# nightLight.net
KiCad netlist of a schematic drawn in EAGLE
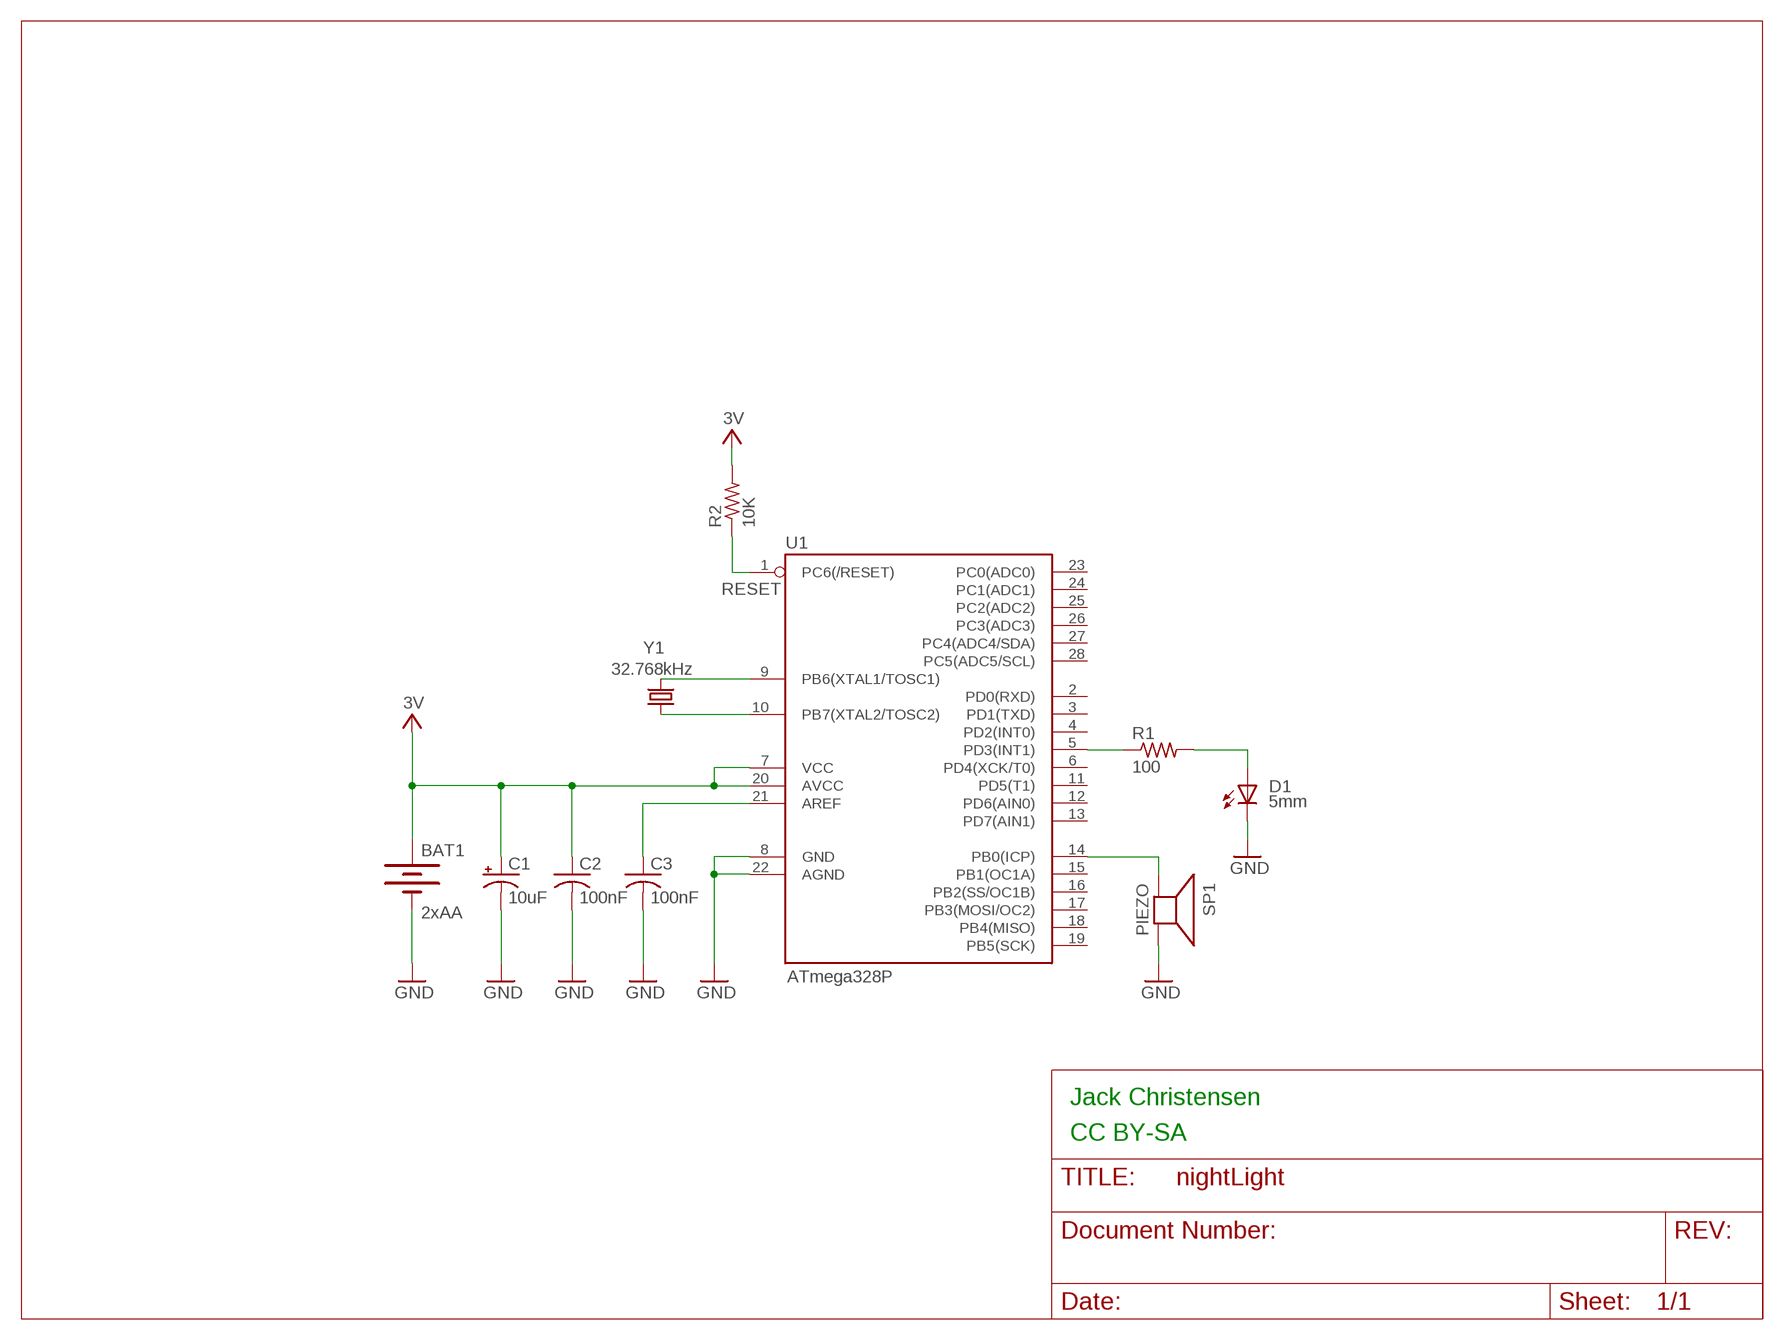
[diagram p0: schematic, sheet 1]

(export (version "E")
  (design (tool "Eeschema 10.0.6"))
  (components
    (comp (ref "BAT1")
      (value "2xAA")
      (footprint "eagle-import:BATTERY-AA")
      (libsource (lib "eagle-import") (part "BATTERYAA"))
    )
    (comp (ref "C1")
      (value "10uF")
      (footprint "eagle-import:E5-4")
      (libsource (lib "eagle-import") (part "CPOL-USE5-4"))
    )
    (comp (ref "C2")
      (value "100nF")
      (footprint "eagle-import:C025-025X050")
      (libsource (lib "eagle-import") (part "C-US025-025X050"))
    )
    (comp (ref "C3")
      (value "100nF")
      (footprint "eagle-import:C025-025X050")
      (libsource (lib "eagle-import") (part "C-US025-025X050"))
    )
    (comp (ref "D1")
      (value "5mm")
      (footprint "eagle-import:LED5MM")
      (libsource (lib "eagle-import") (part "LED5MM"))
    )
    (comp (ref "R1")
      (value "100")
      (footprint "eagle-import:0204_6")
      (libsource (lib "eagle-import") (part "R-US_0204/6"))
    )
    (comp (ref "R2")
      (value "10K")
      (footprint "eagle-import:0204_6")
      (libsource (lib "eagle-import") (part "R-US_0204/6"))
    )
    (comp (ref "SP1")
      (value "PIEZO")
      (footprint "eagle-import:AL11P")
      (libsource (lib "eagle-import") (part "SPEAKER/AL11P"))
    )
    (comp (ref "U1")
      (value "ATmega328P")
      (footprint "eagle-import:DIL28-3")
      (libsource (lib "eagle-import") (part "AVR-MEGA8-PPTH"))
    )
    (comp (ref "Y1")
      (value "32.768kHz")
      (footprint "eagle-import:TC38H")
      (libsource (lib "eagle-import") (part "CRYSTALTC38H"))
    )
  )
  (nets
    (net (code "1") (name "/RESET") (class "Default")
      (node (ref "R2") (pin "1") (pinfunction "1_1") (pintype "passive"))
      (node (ref "U1") (pin "1") (pinfunction "PC6(/RESET)_1") (pintype "bidirectional"))
    )
    (net (code "2") (name "3V") (class "Default")
      (node (ref "BAT1") (pin "PWR@1") (pinfunction "+_PWR@1") (pintype "power_in"))
      (node (ref "C1") (pin "+") (pinfunction "+_+") (pintype "passive"))
      (node (ref "C2") (pin "1") (pinfunction "1_1") (pintype "passive"))
      (node (ref "R2") (pin "2") (pinfunction "2_2") (pintype "passive"))
      (node (ref "U1") (pin "20") (pinfunction "AVCC_20") (pintype "bidirectional"))
      (node (ref "U1") (pin "7") (pinfunction "VCC_7") (pintype "bidirectional"))
    )
    (net (code "3") (name "GND") (class "Default")
      (node (ref "BAT1") (pin "GND@1") (pinfunction "-_GND@1") (pintype "power_in"))
      (node (ref "C1") (pin "-") (pinfunction "-_-") (pintype "passive"))
      (node (ref "C2") (pin "2") (pinfunction "2_2") (pintype "passive"))
      (node (ref "C3") (pin "2") (pinfunction "2_2") (pintype "passive"))
      (node (ref "D1") (pin "K") (pinfunction "C_K") (pintype "passive"))
      (node (ref "SP1") (pin "-") (pinfunction "-_-") (pintype "passive"))
      (node (ref "U1") (pin "22") (pinfunction "AGND_22") (pintype "bidirectional"))
      (node (ref "U1") (pin "8") (pinfunction "GND_8") (pintype "bidirectional"))
    )
    (net (code "4") (name "Net-(D1-PadA)") (class "Default")
      (node (ref "D1") (pin "A") (pinfunction "A_A") (pintype "passive"))
      (node (ref "R1") (pin "2") (pinfunction "2_2") (pintype "passive"))
    )
    (net (code "5") (name "Net-(U1-AREF)") (class "Default")
      (node (ref "C3") (pin "1") (pinfunction "1_1") (pintype "passive"))
      (node (ref "U1") (pin "21") (pinfunction "AREF_21") (pintype "bidirectional"))
    )
    (net (code "6") (name "Net-(U1-PB0(ICP))") (class "Default")
      (node (ref "SP1") (pin "+") (pinfunction "+_+") (pintype "passive"))
      (node (ref "U1") (pin "14") (pinfunction "PB0(ICP)_14") (pintype "bidirectional"))
    )
    (net (code "7") (name "Net-(U1-PB6(XTAL1{slash}TOSC1))") (class "Default")
      (node (ref "U1") (pin "9") (pinfunction "PB6(XTAL1/TOSC1)_9") (pintype "bidirectional"))
      (node (ref "Y1") (pin "2") (pinfunction "2_2") (pintype "passive"))
    )
    (net (code "8") (name "Net-(U1-PB7(XTAL2{slash}TOSC2))") (class "Default")
      (node (ref "U1") (pin "10") (pinfunction "PB7(XTAL2/TOSC2)_10") (pintype "bidirectional"))
      (node (ref "Y1") (pin "1") (pinfunction "1_1") (pintype "passive"))
    )
    (net (code "9") (name "Net-(U1-PD3(INT1))") (class "Default")
      (node (ref "R1") (pin "1") (pinfunction "1_1") (pintype "passive"))
      (node (ref "U1") (pin "5") (pinfunction "PD3(INT1)_5") (pintype "bidirectional"))
    )
    (net (code "10") (name "unconnected-(U1-PB1(OC1A)-Pad15)") (class "Default")
      (node (ref "U1") (pin "15") (pinfunction "PB1(OC1A)_15") (pintype "bidirectional"))
    )
    (net (code "11") (name "unconnected-(U1-PB2(SS{slash}OC1B)-Pad16)") (class "Default")
      (node (ref "U1") (pin "16") (pinfunction "PB2(SS/OC1B)_16") (pintype "bidirectional"))
    )
    (net (code "12") (name "unconnected-(U1-PB3(MOSI{slash}OC2)-Pad17)") (class "Default")
      (node (ref "U1") (pin "17") (pinfunction "PB3(MOSI/OC2)_17") (pintype "bidirectional"))
    )
    (net (code "13") (name "unconnected-(U1-PB4(MISO)-Pad18)") (class "Default")
      (node (ref "U1") (pin "18") (pinfunction "PB4(MISO)_18") (pintype "bidirectional"))
    )
    (net (code "14") (name "unconnected-(U1-PB5(SCK)-Pad19)") (class "Default")
      (node (ref "U1") (pin "19") (pinfunction "PB5(SCK)_19") (pintype "bidirectional"))
    )
    (net (code "15") (name "unconnected-(U1-PC0(ADC0)-Pad23)") (class "Default")
      (node (ref "U1") (pin "23") (pinfunction "PC0(ADC0)_23") (pintype "bidirectional"))
    )
    (net (code "16") (name "unconnected-(U1-PC1(ADC1)-Pad24)") (class "Default")
      (node (ref "U1") (pin "24") (pinfunction "PC1(ADC1)_24") (pintype "bidirectional"))
    )
    (net (code "17") (name "unconnected-(U1-PC2(ADC2)-Pad25)") (class "Default")
      (node (ref "U1") (pin "25") (pinfunction "PC2(ADC2)_25") (pintype "bidirectional"))
    )
    (net (code "18") (name "unconnected-(U1-PC3(ADC3)-Pad26)") (class "Default")
      (node (ref "U1") (pin "26") (pinfunction "PC3(ADC3)_26") (pintype "bidirectional"))
    )
    (net (code "19") (name "unconnected-(U1-PC4(ADC4{slash}SDA)-Pad27)") (class "Default")
      (node (ref "U1") (pin "27") (pinfunction "PC4(ADC4/SDA)_27") (pintype "bidirectional"))
    )
    (net (code "20") (name "unconnected-(U1-PC5(ADC5{slash}SCL)-Pad28)") (class "Default")
      (node (ref "U1") (pin "28") (pinfunction "PC5(ADC5/SCL)_28") (pintype "bidirectional"))
    )
    (net (code "21") (name "unconnected-(U1-PD0(RXD)-Pad2)") (class "Default")
      (node (ref "U1") (pin "2") (pinfunction "PD0(RXD)_2") (pintype "bidirectional"))
    )
    (net (code "22") (name "unconnected-(U1-PD1(TXD)-Pad3)") (class "Default")
      (node (ref "U1") (pin "3") (pinfunction "PD1(TXD)_3") (pintype "bidirectional"))
    )
    (net (code "23") (name "unconnected-(U1-PD2(INT0)-Pad4)") (class "Default")
      (node (ref "U1") (pin "4") (pinfunction "PD2(INT0)_4") (pintype "bidirectional"))
    )
    (net (code "24") (name "unconnected-(U1-PD4(XCK{slash}T0)-Pad6)") (class "Default")
      (node (ref "U1") (pin "6") (pinfunction "PD4(XCK/T0)_6") (pintype "bidirectional"))
    )
    (net (code "25") (name "unconnected-(U1-PD5(T1)-Pad11)") (class "Default")
      (node (ref "U1") (pin "11") (pinfunction "PD5(T1)_11") (pintype "bidirectional"))
    )
    (net (code "26") (name "unconnected-(U1-PD6(AIN0)-Pad12)") (class "Default")
      (node (ref "U1") (pin "12") (pinfunction "PD6(AIN0)_12") (pintype "bidirectional"))
    )
    (net (code "27") (name "unconnected-(U1-PD7(AIN1)-Pad13)") (class "Default")
      (node (ref "U1") (pin "13") (pinfunction "PD7(AIN1)_13") (pintype "bidirectional"))
    )
  )
)
